# DarkRoom.net
KiCad netlist of a schematic drawn in EAGLE
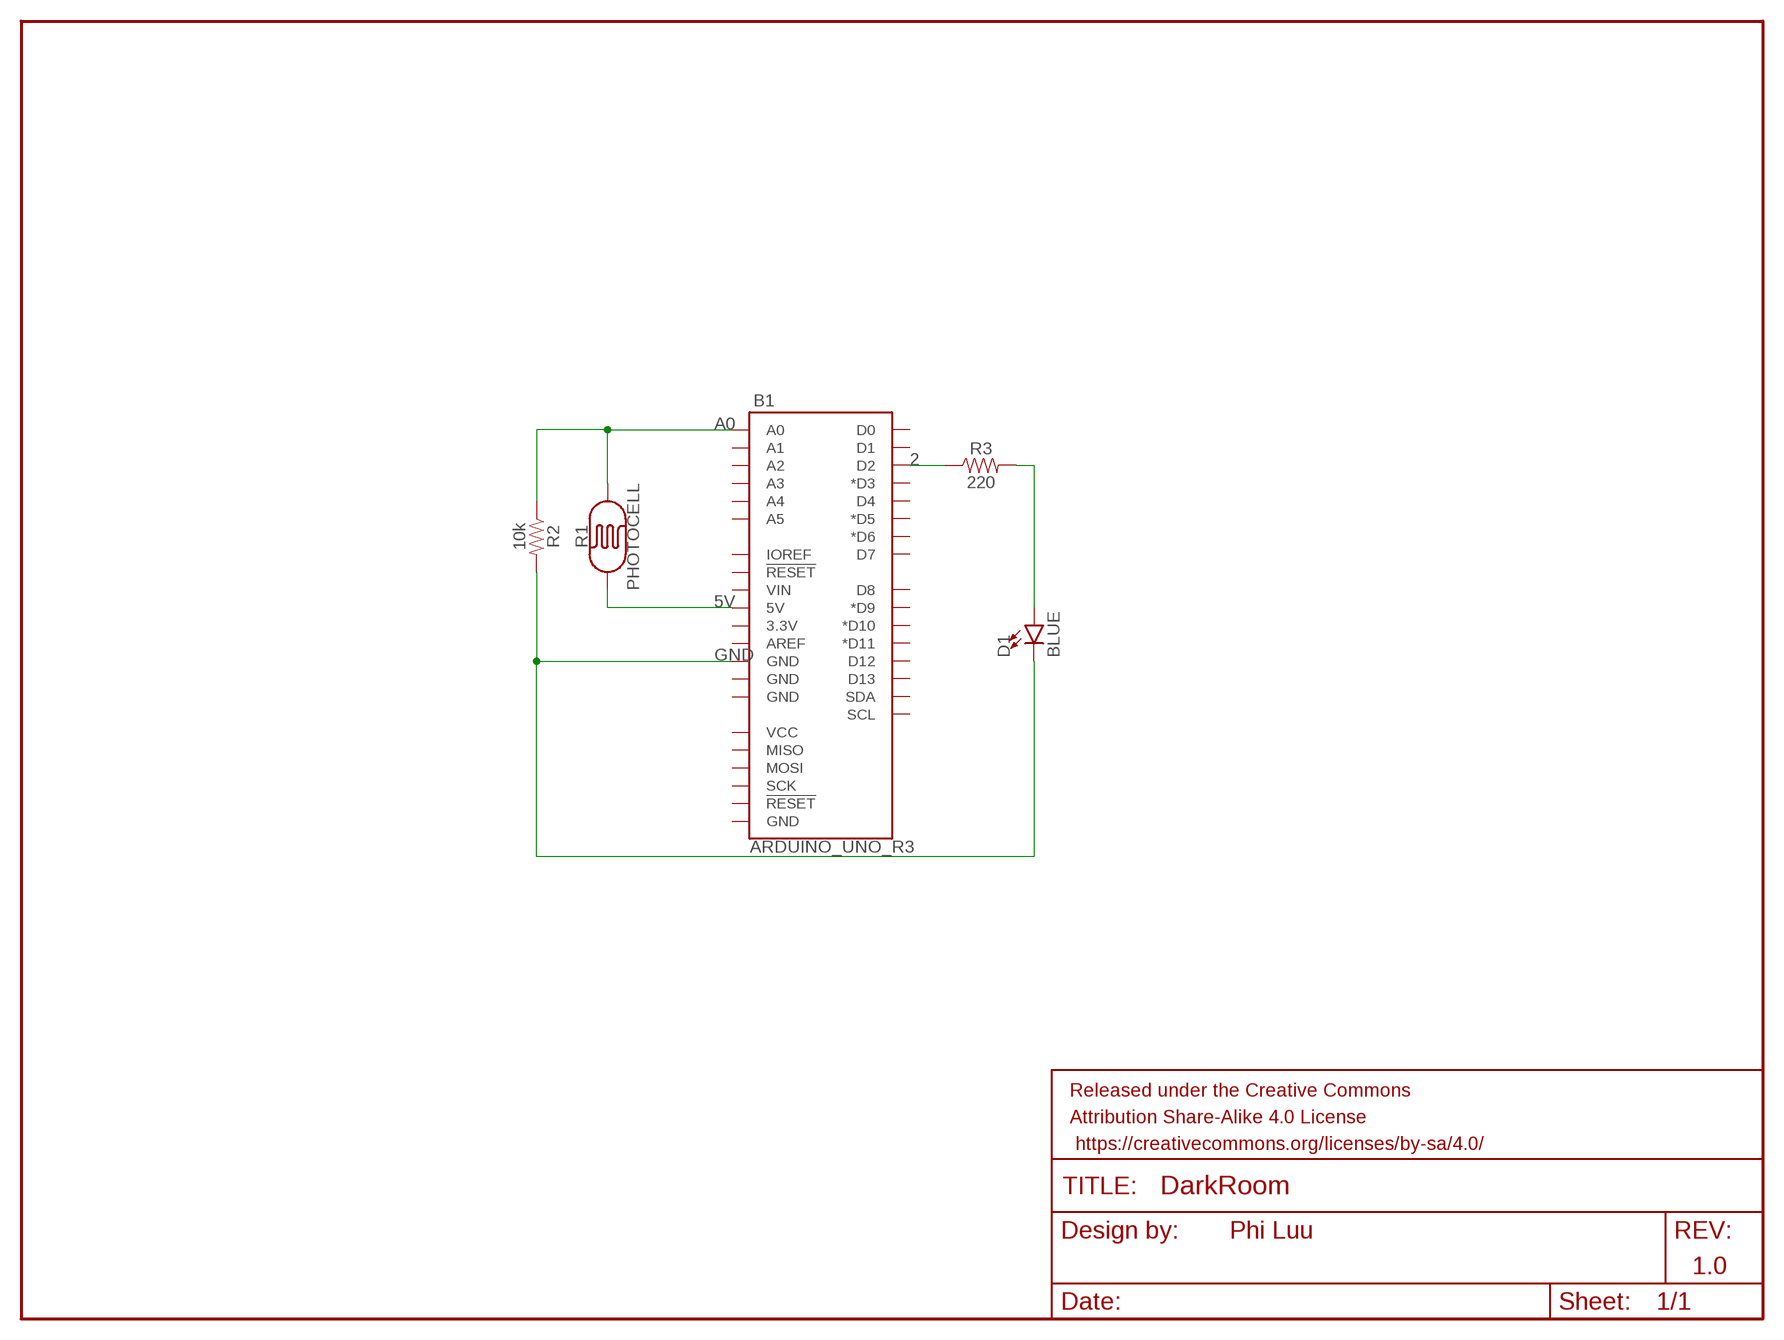
[diagram p0: schematic, sheet 1]

(export (version "E")
  (design (tool "Eeschema 10.0.6"))
  (components
    (comp (ref "B1")
      (value "ARDUINO_UNO_R3")
      (footprint "eagle-import:ARDUINO_R3")
      (libsource (lib "eagle-import") (part "ARDUINO_UNO_R3"))
    )
    (comp (ref "D1")
      (value "BLUE")
      (footprint "eagle-import:LED_5MM")
      (libsource (lib "eagle-import") (part "LED5MM"))
    )
    (comp (ref "FRAME1")
      (value "FRAME-LETTER")
      (footprint "eagle-import:CREATIVE_COMMONS")
      (libsource (lib "eagle-import") (part "FRAME-LETTER"))
    )
    (comp (ref "R1")
      (value "PHOTOCELL")
      (footprint "eagle-import:PHOTOCELL")
      (libsource (lib "eagle-import") (part "PHOTOCELLPTH"))
    )
    (comp (ref "R2")
      (value "10k")
      (footprint "eagle-import:AXIAL-0.3")
      (libsource (lib "eagle-import") (part "10KOHM-HORIZ-1/4W-5%"))
    )
    (comp (ref "R3")
      (value "220")
      (footprint "eagle-import:AXIAL-0.3")
      (libsource (lib "eagle-import") (part "10KOHM-HORIZ-1/4W-5%"))
    )
  )
  (nets
    (net (code "1") (name "/2") (class "Default")
      (node (ref "B1") (pin "D2") (pinfunction "D2_D2") (pintype "bidirectional"))
      (node (ref "R3") (pin "P$1") (pinfunction "1_P$1") (pintype "passive"))
    )
    (net (code "2") (name "/5V") (class "Default")
      (node (ref "B1") (pin "5V") (pinfunction "5V_5V") (pintype "bidirectional"))
      (node (ref "R1") (pin "1") (pinfunction "P$1_1") (pintype "bidirectional"))
    )
    (net (code "3") (name "/A0") (class "Default")
      (node (ref "B1") (pin "A0") (pinfunction "A0_A0") (pintype "bidirectional"))
      (node (ref "R1") (pin "2") (pinfunction "P$2_2") (pintype "bidirectional"))
      (node (ref "R2") (pin "P$1") (pinfunction "1_P$1") (pintype "passive"))
    )
    (net (code "4") (name "/GND") (class "Default")
      (node (ref "B1") (pin "GND@4") (pinfunction "GND_GND@4") (pintype "bidirectional"))
      (node (ref "D1") (pin "K") (pinfunction "C_K") (pintype "passive"))
      (node (ref "R2") (pin "P$2") (pinfunction "2_P$2") (pintype "passive"))
    )
    (net (code "5") (name "Net-(R3-2)") (class "Default")
      (node (ref "D1") (pin "A") (pinfunction "A_A") (pintype "passive"))
      (node (ref "R3") (pin "P$2") (pinfunction "2_P$2") (pintype "passive"))
    )
    (net (code "6") (name "unconnected-(B1-*D3-PadD3)") (class "Default")
      (node (ref "B1") (pin "D3") (pinfunction "*D3_D3") (pintype "bidirectional"))
    )
    (net (code "7") (name "unconnected-(B1-*D5-PadD5)") (class "Default")
      (node (ref "B1") (pin "D5") (pinfunction "*D5_D5") (pintype "bidirectional"))
    )
    (net (code "8") (name "unconnected-(B1-*D6-PadD6)") (class "Default")
      (node (ref "B1") (pin "D6") (pinfunction "*D6_D6") (pintype "bidirectional"))
    )
    (net (code "9") (name "unconnected-(B1-*D9-PadD9)") (class "Default")
      (node (ref "B1") (pin "D9") (pinfunction "*D9_D9") (pintype "bidirectional"))
    )
    (net (code "10") (name "unconnected-(B1-*D10-PadD10)") (class "Default")
      (node (ref "B1") (pin "D10") (pinfunction "*D10_D10") (pintype "bidirectional"))
    )
    (net (code "11") (name "unconnected-(B1-*D11-PadD11)") (class "Default")
      (node (ref "B1") (pin "D11") (pinfunction "*D11_D11") (pintype "bidirectional"))
    )
    (net (code "12") (name "unconnected-(B1-GND-PadGND@1)") (class "Default")
      (node (ref "B1") (pin "GND@1") (pinfunction "GND_GND@1") (pintype "bidirectional"))
    )
    (net (code "13") (name "unconnected-(B1-GND-PadGND@2)") (class "Default")
      (node (ref "B1") (pin "GND@2") (pinfunction "GND_GND@2") (pintype "bidirectional"))
    )
    (net (code "14") (name "unconnected-(B1-GND-PadGND@3)") (class "Default")
      (node (ref "B1") (pin "GND@3") (pinfunction "GND_GND@3") (pintype "bidirectional"))
    )
    (net (code "15") (name "unconnected-(B1-Pad3.3V)") (class "Default")
      (node (ref "B1") (pin "3.3V") (pinfunction "3.3V_3.3V") (pintype "bidirectional"))
    )
    (net (code "16") (name "unconnected-(B1-PadA1)") (class "Default")
      (node (ref "B1") (pin "A1") (pinfunction "A1_A1") (pintype "bidirectional"))
    )
    (net (code "17") (name "unconnected-(B1-PadA2)") (class "Default")
      (node (ref "B1") (pin "A2") (pinfunction "A2_A2") (pintype "bidirectional"))
    )
    (net (code "18") (name "unconnected-(B1-PadA3)") (class "Default")
      (node (ref "B1") (pin "A3") (pinfunction "A3_A3") (pintype "bidirectional"))
    )
    (net (code "19") (name "unconnected-(B1-PadA4)") (class "Default")
      (node (ref "B1") (pin "A4") (pinfunction "A4_A4") (pintype "bidirectional"))
    )
    (net (code "20") (name "unconnected-(B1-PadA5)") (class "Default")
      (node (ref "B1") (pin "A5") (pinfunction "A5_A5") (pintype "bidirectional"))
    )
    (net (code "21") (name "unconnected-(B1-PadAREF)") (class "Default")
      (node (ref "B1") (pin "AREF") (pinfunction "AREF_AREF") (pintype "bidirectional"))
    )
    (net (code "22") (name "unconnected-(B1-PadD0)") (class "Default")
      (node (ref "B1") (pin "D0") (pinfunction "D0_D0") (pintype "bidirectional"))
    )
    (net (code "23") (name "unconnected-(B1-PadD1)") (class "Default")
      (node (ref "B1") (pin "D1") (pinfunction "D1_D1") (pintype "bidirectional"))
    )
    (net (code "24") (name "unconnected-(B1-PadD4)") (class "Default")
      (node (ref "B1") (pin "D4") (pinfunction "D4_D4") (pintype "bidirectional"))
    )
    (net (code "25") (name "unconnected-(B1-PadD7)") (class "Default")
      (node (ref "B1") (pin "D7") (pinfunction "D7_D7") (pintype "bidirectional"))
    )
    (net (code "26") (name "unconnected-(B1-PadD8)") (class "Default")
      (node (ref "B1") (pin "D8") (pinfunction "D8_D8") (pintype "bidirectional"))
    )
    (net (code "27") (name "unconnected-(B1-PadD12)") (class "Default")
      (node (ref "B1") (pin "D12") (pinfunction "D12_D12") (pintype "bidirectional"))
    )
    (net (code "28") (name "unconnected-(B1-PadD13)") (class "Default")
      (node (ref "B1") (pin "D13") (pinfunction "D13_D13") (pintype "bidirectional"))
    )
    (net (code "29") (name "unconnected-(B1-PadIOREF)") (class "Default")
      (node (ref "B1") (pin "IOREF") (pinfunction "IOREF_IOREF") (pintype "bidirectional"))
    )
    (net (code "30") (name "unconnected-(B1-PadMISO)") (class "Default")
      (node (ref "B1") (pin "MISO") (pinfunction "MISO_MISO") (pintype "bidirectional"))
    )
    (net (code "31") (name "unconnected-(B1-PadMOSI)") (class "Default")
      (node (ref "B1") (pin "MOSI") (pinfunction "MOSI_MOSI") (pintype "bidirectional"))
    )
    (net (code "32") (name "unconnected-(B1-PadSCK)") (class "Default")
      (node (ref "B1") (pin "SCK") (pinfunction "SCK_SCK") (pintype "bidirectional"))
    )
    (net (code "33") (name "unconnected-(B1-PadSCL)") (class "Default")
      (node (ref "B1") (pin "SCL") (pinfunction "SCL_SCL") (pintype "bidirectional"))
    )
    (net (code "34") (name "unconnected-(B1-PadSDA)") (class "Default")
      (node (ref "B1") (pin "SDA") (pinfunction "SDA_SDA") (pintype "bidirectional"))
    )
    (net (code "35") (name "unconnected-(B1-PadVCC)") (class "Default")
      (node (ref "B1") (pin "VCC") (pinfunction "VCC_VCC") (pintype "bidirectional"))
    )
    (net (code "36") (name "unconnected-(B1-PadVIN)") (class "Default")
      (node (ref "B1") (pin "VIN") (pinfunction "VIN_VIN") (pintype "bidirectional"))
    )
    (net (code "37") (name "unconnected-(B1-~{RESET}-PadRESET@1)") (class "Default")
      (node (ref "B1") (pin "RESET@1") (pinfunction "~{RESET}_RESET@1") (pintype "bidirectional"))
    )
    (net (code "38") (name "unconnected-(B1-~{RESET}-PadRESET@2)") (class "Default")
      (node (ref "B1") (pin "RESET@2") (pinfunction "~{RESET}_RESET@2") (pintype "bidirectional"))
    )
  )
)
